# IN-2Module.net
KiCad netlist of a schematic drawn in EAGLE
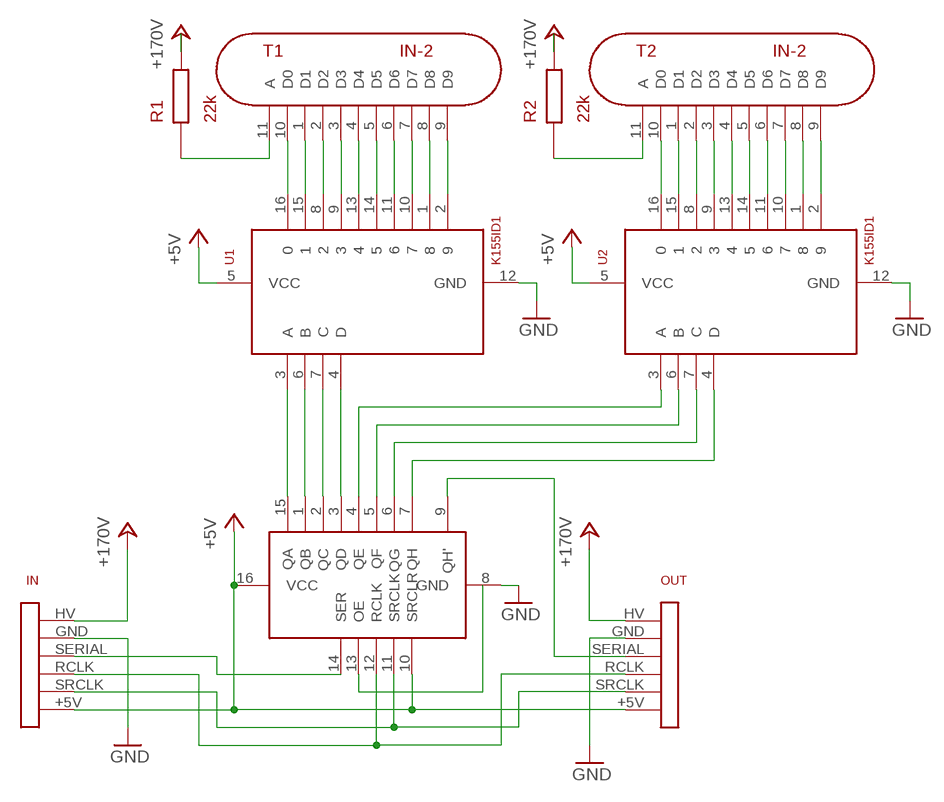
[diagram p0: schematic, sheet 1]

(export (version "E")
  (design (tool "Eeschema 10.0.6"))
  (components
    (comp (ref "IN")
      (value "NIXIE_INTERCONNECT")
      (footprint "eagle-import:NIXIE_INTERCONNECT")
      (libsource (lib "eagle-import") (part "NIXIE_INTERCONNECT"))
    )
    (comp (ref "OUT")
      (value "NIXIE_INTERCONNECT")
      (footprint "eagle-import:NIXIE_INTERCONNECT")
      (libsource (lib "eagle-import") (part "NIXIE_INTERCONNECT"))
    )
    (comp (ref "R1")
      (value "22k")
      (footprint "eagle-import:ANODE_RESISTOR")
      (libsource (lib "eagle-import") (part "ANODE_RESISTOR"))
    )
    (comp (ref "R2")
      (value "22k")
      (footprint "eagle-import:ANODE_RESISTOR")
      (libsource (lib "eagle-import") (part "ANODE_RESISTOR"))
    )
    (comp (ref "T1")
      (value "IN-2")
      (footprint "eagle-import:IN-2")
      (libsource (lib "eagle-import") (part "IN-2"))
    )
    (comp (ref "T2")
      (value "IN-2")
      (footprint "eagle-import:IN-2")
      (libsource (lib "eagle-import") (part "IN-2"))
    )
    (comp (ref "U1")
      (value "K155ID1")
      (footprint "eagle-import:DIP16-2.54-19.2X7.62MM")
      (libsource (lib "eagle-import") (part "K155ID1"))
    )
    (comp (ref "U2")
      (value "K155ID1")
      (footprint "eagle-import:DIP16-2.54-19.2X7.62MM")
      (libsource (lib "eagle-import") (part "K155ID1"))
    )
    (comp (ref "U3")
      (value "74HC595")
      (footprint "eagle-import:DIL16")
      (libsource (lib "eagle-import") (part "74HC595"))
    )
  )
  (nets
    (net (code "1") (name "+5V") (class "Default")
      (node (ref "IN") (pin "+5V") (pinfunction "+5V_+5V") (pintype "bidirectional"))
      (node (ref "OUT") (pin "+5V") (pinfunction "+5V_+5V") (pintype "bidirectional"))
      (node (ref "U1") (pin "5") (pinfunction "VCC_5") (pintype "bidirectional"))
      (node (ref "U2") (pin "5") (pinfunction "VCC_5") (pintype "bidirectional"))
      (node (ref "U3") (pin "10") (pinfunction "SRCLR_10") (pintype "bidirectional"))
      (node (ref "U3") (pin "16") (pinfunction "VCC_16") (pintype "bidirectional"))
    )
    (net (code "2") (name "+170V") (class "Default")
      (node (ref "IN") (pin "HV") (pinfunction "HV_HV") (pintype "bidirectional"))
      (node (ref "OUT") (pin "HV") (pinfunction "HV_HV") (pintype "bidirectional"))
      (node (ref "R1") (pin "P$2") (pinfunction "P$2_P$2") (pintype "bidirectional"))
      (node (ref "R2") (pin "P$2") (pinfunction "P$2_P$2") (pintype "bidirectional"))
    )
    (net (code "3") (name "GND") (class "Default")
      (node (ref "IN") (pin "GND") (pinfunction "GND_GND") (pintype "bidirectional"))
      (node (ref "OUT") (pin "GND") (pinfunction "GND_GND") (pintype "bidirectional"))
      (node (ref "U1") (pin "12") (pinfunction "GND_12") (pintype "bidirectional"))
      (node (ref "U2") (pin "12") (pinfunction "GND_12") (pintype "bidirectional"))
      (node (ref "U3") (pin "8") (pinfunction "GND_8") (pintype "bidirectional"))
    )
    (net (code "4") (name "Net-(T1-A)") (class "Default")
      (node (ref "R1") (pin "P$1") (pinfunction "P$1_P$1") (pintype "bidirectional"))
      (node (ref "T1") (pin "11") (pinfunction "A_11") (pintype "bidirectional"))
    )
    (net (code "5") (name "Net-(T1-D0)") (class "Default")
      (node (ref "T1") (pin "10") (pinfunction "D0_10") (pintype "bidirectional"))
      (node (ref "U1") (pin "16") (pinfunction "0_16") (pintype "bidirectional"))
    )
    (net (code "6") (name "Net-(T1-D1)") (class "Default")
      (node (ref "T1") (pin "1") (pinfunction "D1_1") (pintype "bidirectional"))
      (node (ref "U1") (pin "15") (pinfunction "1_15") (pintype "bidirectional"))
    )
    (net (code "7") (name "Net-(T1-D2)") (class "Default")
      (node (ref "T1") (pin "2") (pinfunction "D2_2") (pintype "bidirectional"))
      (node (ref "U1") (pin "8") (pinfunction "2_8") (pintype "bidirectional"))
    )
    (net (code "8") (name "Net-(T1-D3)") (class "Default")
      (node (ref "T1") (pin "3") (pinfunction "D3_3") (pintype "bidirectional"))
      (node (ref "U1") (pin "9") (pinfunction "3_9") (pintype "bidirectional"))
    )
    (net (code "9") (name "Net-(T1-D4)") (class "Default")
      (node (ref "T1") (pin "4") (pinfunction "D4_4") (pintype "bidirectional"))
      (node (ref "U1") (pin "13") (pinfunction "4_13") (pintype "bidirectional"))
    )
    (net (code "10") (name "Net-(T1-D5)") (class "Default")
      (node (ref "T1") (pin "5") (pinfunction "D5_5") (pintype "bidirectional"))
      (node (ref "U1") (pin "14") (pinfunction "5_14") (pintype "bidirectional"))
    )
    (net (code "11") (name "Net-(T1-D6)") (class "Default")
      (node (ref "T1") (pin "6") (pinfunction "D6_6") (pintype "bidirectional"))
      (node (ref "U1") (pin "11") (pinfunction "6_11") (pintype "bidirectional"))
    )
    (net (code "12") (name "Net-(T1-D7)") (class "Default")
      (node (ref "T1") (pin "7") (pinfunction "D7_7") (pintype "bidirectional"))
      (node (ref "U1") (pin "10") (pinfunction "7_10") (pintype "bidirectional"))
    )
    (net (code "13") (name "Net-(T1-D8)") (class "Default")
      (node (ref "T1") (pin "8") (pinfunction "D8_8") (pintype "bidirectional"))
      (node (ref "U1") (pin "1") (pinfunction "8_1") (pintype "bidirectional"))
    )
    (net (code "14") (name "Net-(T1-D9)") (class "Default")
      (node (ref "T1") (pin "9") (pinfunction "D9_9") (pintype "bidirectional"))
      (node (ref "U1") (pin "2") (pinfunction "9_2") (pintype "bidirectional"))
    )
    (net (code "15") (name "Net-(T2-A)") (class "Default")
      (node (ref "R2") (pin "P$1") (pinfunction "P$1_P$1") (pintype "bidirectional"))
      (node (ref "T2") (pin "11") (pinfunction "A_11") (pintype "bidirectional"))
    )
    (net (code "16") (name "Net-(T2-D0)") (class "Default")
      (node (ref "T2") (pin "10") (pinfunction "D0_10") (pintype "bidirectional"))
      (node (ref "U2") (pin "16") (pinfunction "0_16") (pintype "bidirectional"))
    )
    (net (code "17") (name "Net-(T2-D1)") (class "Default")
      (node (ref "T2") (pin "1") (pinfunction "D1_1") (pintype "bidirectional"))
      (node (ref "U2") (pin "15") (pinfunction "1_15") (pintype "bidirectional"))
    )
    (net (code "18") (name "Net-(T2-D2)") (class "Default")
      (node (ref "T2") (pin "2") (pinfunction "D2_2") (pintype "bidirectional"))
      (node (ref "U2") (pin "8") (pinfunction "2_8") (pintype "bidirectional"))
    )
    (net (code "19") (name "Net-(T2-D3)") (class "Default")
      (node (ref "T2") (pin "3") (pinfunction "D3_3") (pintype "bidirectional"))
      (node (ref "U2") (pin "9") (pinfunction "3_9") (pintype "bidirectional"))
    )
    (net (code "20") (name "Net-(T2-D4)") (class "Default")
      (node (ref "T2") (pin "4") (pinfunction "D4_4") (pintype "bidirectional"))
      (node (ref "U2") (pin "13") (pinfunction "4_13") (pintype "bidirectional"))
    )
    (net (code "21") (name "Net-(T2-D5)") (class "Default")
      (node (ref "T2") (pin "5") (pinfunction "D5_5") (pintype "bidirectional"))
      (node (ref "U2") (pin "14") (pinfunction "5_14") (pintype "bidirectional"))
    )
    (net (code "22") (name "Net-(T2-D6)") (class "Default")
      (node (ref "T2") (pin "6") (pinfunction "D6_6") (pintype "bidirectional"))
      (node (ref "U2") (pin "11") (pinfunction "6_11") (pintype "bidirectional"))
    )
    (net (code "23") (name "Net-(T2-D7)") (class "Default")
      (node (ref "T2") (pin "7") (pinfunction "D7_7") (pintype "bidirectional"))
      (node (ref "U2") (pin "10") (pinfunction "7_10") (pintype "bidirectional"))
    )
    (net (code "24") (name "Net-(T2-D8)") (class "Default")
      (node (ref "T2") (pin "8") (pinfunction "D8_8") (pintype "bidirectional"))
      (node (ref "U2") (pin "1") (pinfunction "8_1") (pintype "bidirectional"))
    )
    (net (code "25") (name "Net-(T2-D9)") (class "Default")
      (node (ref "T2") (pin "9") (pinfunction "D9_9") (pintype "bidirectional"))
      (node (ref "U2") (pin "2") (pinfunction "9_2") (pintype "bidirectional"))
    )
    (net (code "26") (name "Net-(U1-A)") (class "Default")
      (node (ref "U1") (pin "3") (pinfunction "A_3") (pintype "bidirectional"))
      (node (ref "U3") (pin "15") (pinfunction "QA_15") (pintype "bidirectional"))
    )
    (net (code "27") (name "Net-(U1-B)") (class "Default")
      (node (ref "U1") (pin "6") (pinfunction "B_6") (pintype "bidirectional"))
      (node (ref "U3") (pin "1") (pinfunction "QB_1") (pintype "bidirectional"))
    )
    (net (code "28") (name "Net-(U1-C)") (class "Default")
      (node (ref "U1") (pin "7") (pinfunction "C_7") (pintype "bidirectional"))
      (node (ref "U3") (pin "2") (pinfunction "QC_2") (pintype "bidirectional"))
    )
    (net (code "29") (name "Net-(U1-D)") (class "Default")
      (node (ref "U1") (pin "4") (pinfunction "D_4") (pintype "bidirectional"))
      (node (ref "U3") (pin "3") (pinfunction "QD_3") (pintype "bidirectional"))
    )
    (net (code "30") (name "Net-(U2-A)") (class "Default")
      (node (ref "U2") (pin "3") (pinfunction "A_3") (pintype "bidirectional"))
      (node (ref "U3") (pin "4") (pinfunction "QE_4") (pintype "bidirectional"))
    )
    (net (code "31") (name "Net-(U2-B)") (class "Default")
      (node (ref "U2") (pin "6") (pinfunction "B_6") (pintype "bidirectional"))
      (node (ref "U3") (pin "5") (pinfunction "QF_5") (pintype "bidirectional"))
    )
    (net (code "32") (name "Net-(U2-C)") (class "Default")
      (node (ref "U2") (pin "7") (pinfunction "C_7") (pintype "bidirectional"))
      (node (ref "U3") (pin "6") (pinfunction "QG_6") (pintype "bidirectional"))
    )
    (net (code "33") (name "Net-(U2-D)") (class "Default")
      (node (ref "U2") (pin "4") (pinfunction "D_4") (pintype "bidirectional"))
      (node (ref "U3") (pin "7") (pinfunction "QH_7") (pintype "bidirectional"))
    )
    (net (code "34") (name "Net-(U3-QH')") (class "Default")
      (node (ref "OUT") (pin "SERIAL") (pinfunction "SERIAL_SERIAL") (pintype "bidirectional"))
      (node (ref "U3") (pin "9") (pinfunction "QH'_9") (pintype "bidirectional"))
    )
    (net (code "35") (name "Net-(U3-RCLK)") (class "Default")
      (node (ref "IN") (pin "RCLK") (pinfunction "RCLK_RCLK") (pintype "bidirectional"))
      (node (ref "OUT") (pin "RCLK") (pinfunction "RCLK_RCLK") (pintype "bidirectional"))
      (node (ref "U3") (pin "12") (pinfunction "RCLK_12") (pintype "bidirectional"))
    )
    (net (code "36") (name "Net-(U3-SER)") (class "Default")
      (node (ref "IN") (pin "SERIAL") (pinfunction "SERIAL_SERIAL") (pintype "bidirectional"))
      (node (ref "U3") (pin "14") (pinfunction "SER_14") (pintype "bidirectional"))
    )
    (net (code "37") (name "Net-(U3-SRCLK)") (class "Default")
      (node (ref "IN") (pin "SRCLK") (pinfunction "SRCLK_SRCLK") (pintype "bidirectional"))
      (node (ref "OUT") (pin "SRCLK") (pinfunction "SRCLK_SRCLK") (pintype "bidirectional"))
      (node (ref "U3") (pin "11") (pinfunction "SRCLK_11") (pintype "bidirectional"))
    )
    (net (code "38") (name "unconnected-(U3-OE-Pad13)") (class "Default")
      (node (ref "U3") (pin "13") (pinfunction "OE_13") (pintype "bidirectional"))
    )
  )
)
